# USB.net
KiCad netlist of a schematic drawn in Altium Designer
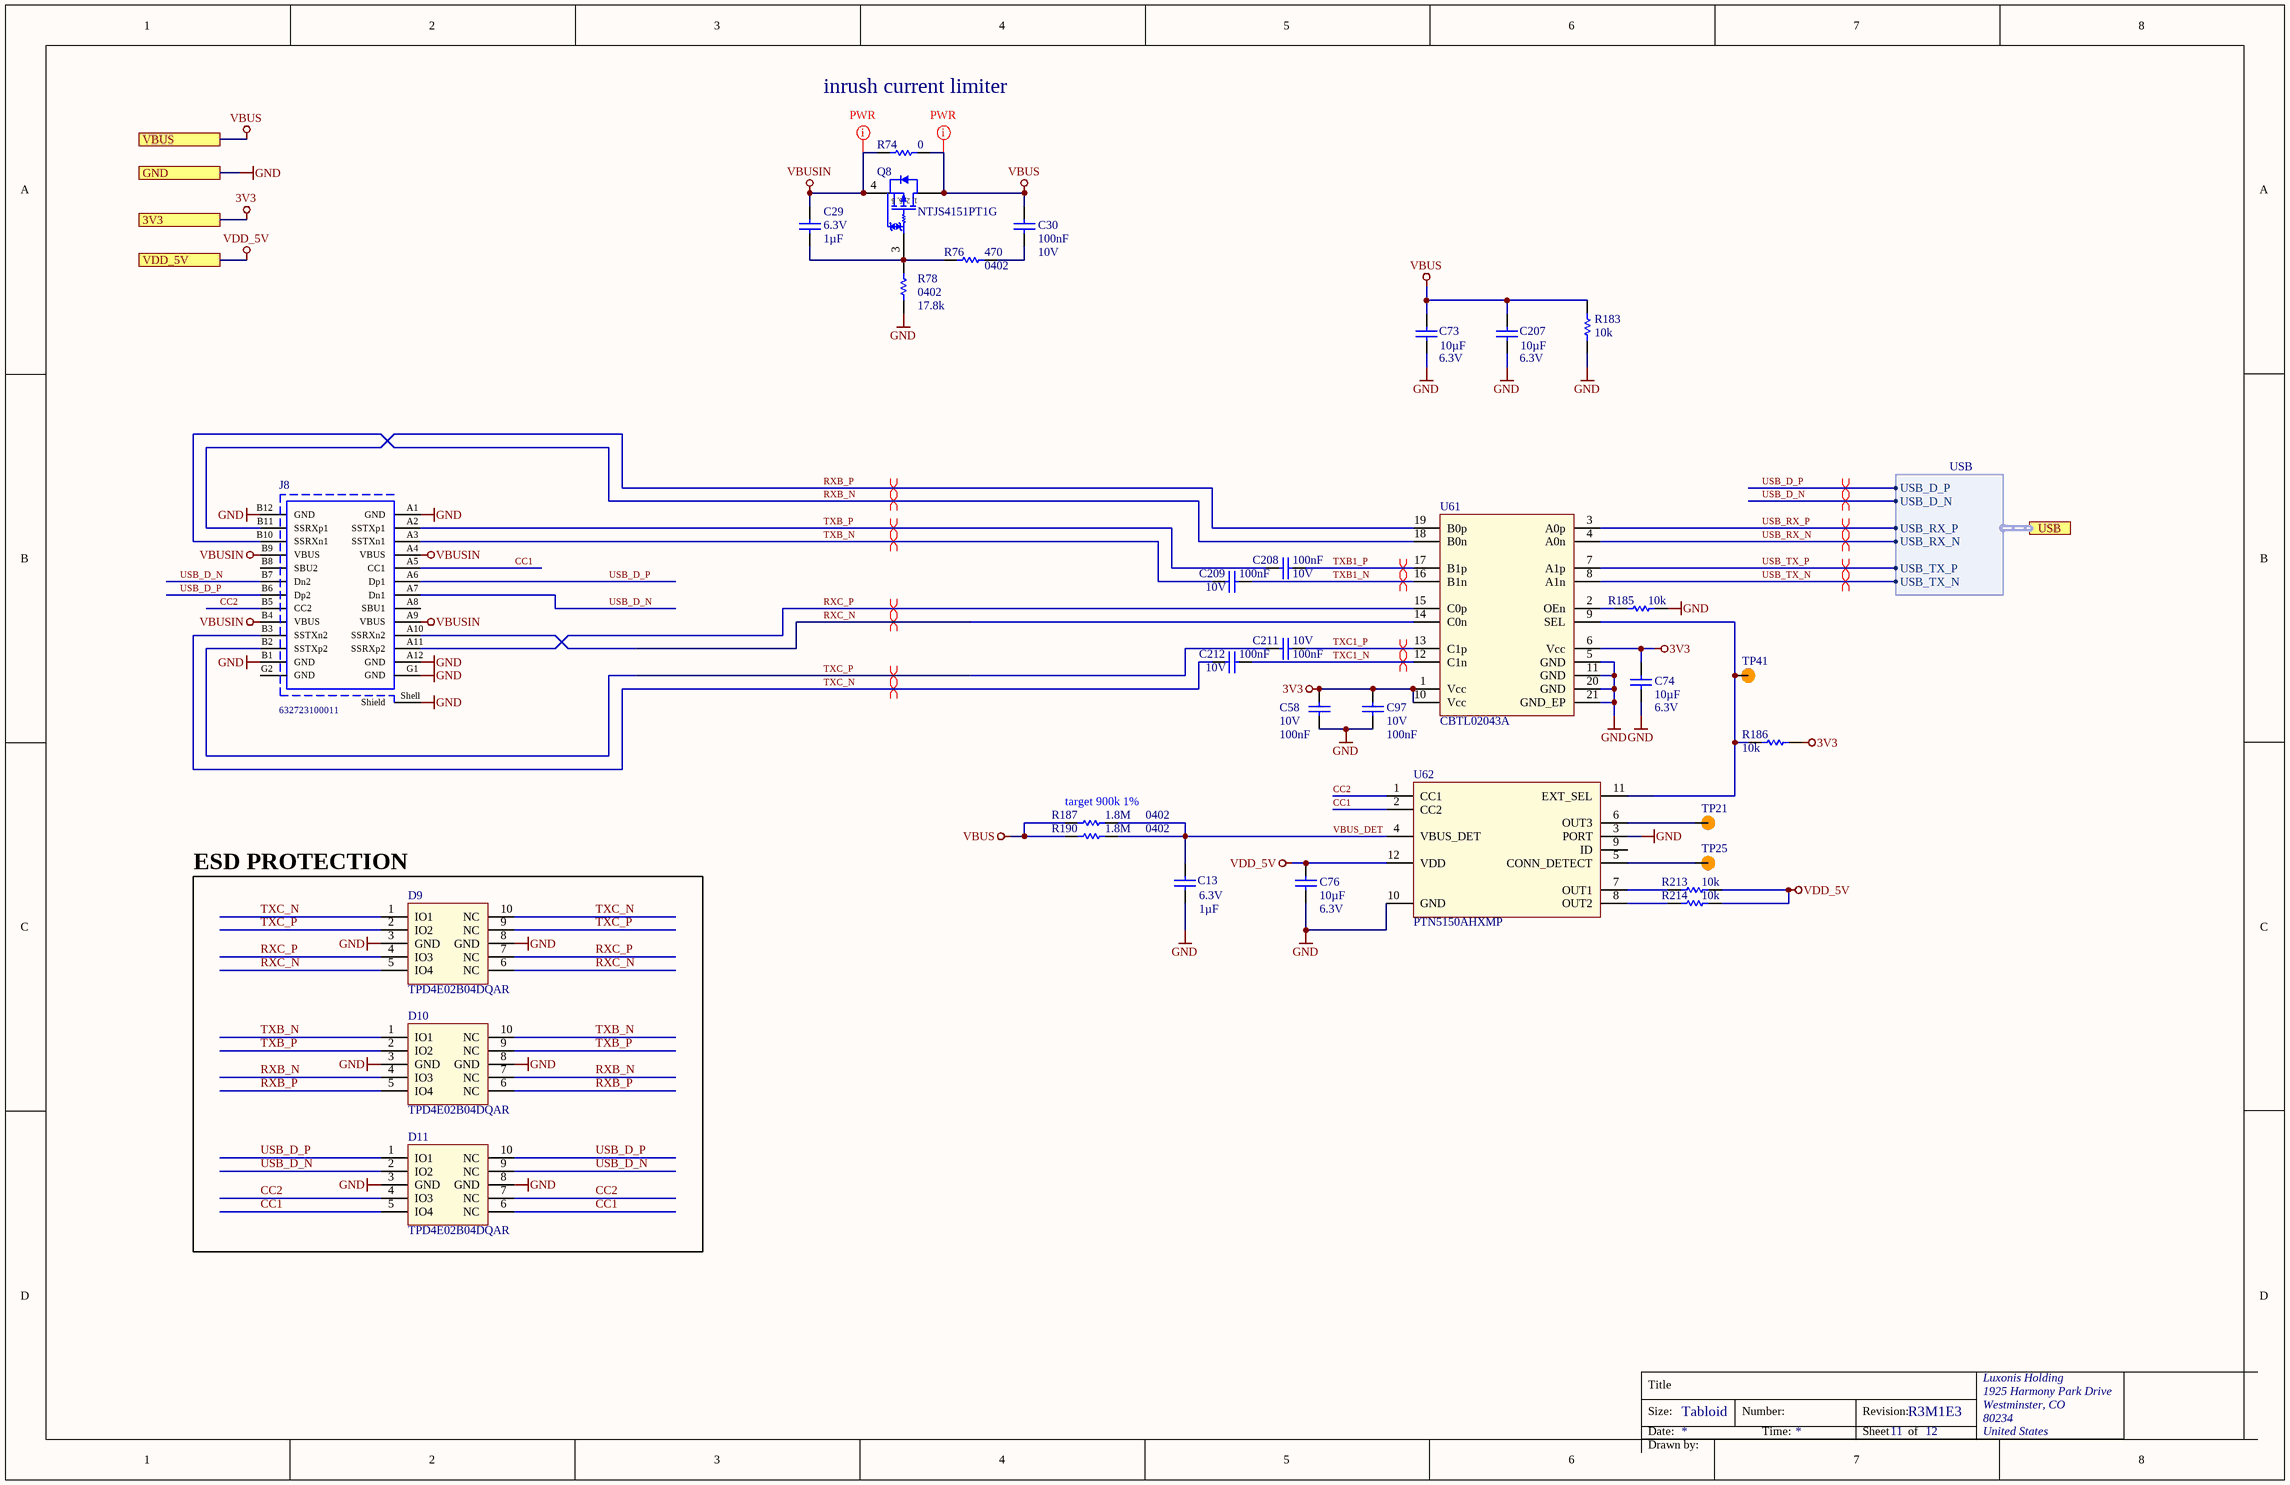
[diagram p0: USB.SchDoc]

(export (version "E")
  (design (tool "Eeschema 10.0.6"))
  (components
    (comp (ref "C13")
      (value "1µF")
      (footprint "CAPC0201(0603)33_L")
      (description "CAP CER 1UF 6.3V X5R 0201 20%")
      (fields
        (field (name "TOLERANCE") "20%")
        (field (name "VOLTAGE RATING") "6.3V")
        (field (name "Comment") "GRM033R60J105MEA2D")
      )
      (libsource (lib "Luxonis LLC") (part "LLL153C70G474ME17E"))
    )
    (comp (ref "C29")
      (value "1µF")
      (footprint "CAPC0201(0603)33_L")
      (description "CAP CER 1UF 6.3V X5R 0201 20%")
      (fields
        (field (name "TOLERANCE") "20%")
        (field (name "VOLTAGE RATING") "6.3V")
        (field (name "Comment") "GRM033R60J105MEA2D")
      )
      (libsource (lib "Luxonis LLC") (part "LLL153C70G474ME17E"))
    )
    (comp (ref "C30")
      (value "100nF")
      (footprint "CAPC0201(0603)33_L")
      (description "CAP CER 0.1UF 10V X5R 0201 10%")
      (fields
        (field (name "TOLERANCE") "10%")
        (field (name "VOLTAGE RATING") "10V")
        (field (name "Comment") "GRM033R61A104KE15D")
      )
      (libsource (lib "Luxonis LLC") (part "LLL153C70G474ME17E"))
    )
    (comp (ref "C58")
      (value "100nF")
      (footprint "CAPC0201(0603)33_L")
      (description "CAP CER 0.1UF 10V X5R 0201 10%")
      (fields
        (field (name "TOLERANCE") "10%")
        (field (name "VOLTAGE RATING") "10V")
        (field (name "Comment") "GRM033R61A104KE15D")
      )
      (libsource (lib "Luxonis LLC") (part "LLL153C70G474ME17E"))
    )
    (comp (ref "C73")
      (value "10µF")
      (footprint "CAPC0402(1005)70_N")
      (description "CAP CER 10UF 6.3V X5R 0402 20%")
      (fields
        (field (name "TOLERANCE") "20%")
        (field (name "VOLTAGE RATING") "6.3V")
        (field (name "Comment") "GRM155R60J106ME15D")
      )
      (libsource (lib "Luxonis LLC") (part "LLL153C70G474ME17E"))
    )
    (comp (ref "C74")
      (value "10µF")
      (footprint "CAPC0402(1005)70_N")
      (description "CAP CER 10UF 6.3V X5R 0402 20%")
      (fields
        (field (name "TOLERANCE") "20%")
        (field (name "VOLTAGE RATING") "6.3V")
        (field (name "Comment") "GRM155R60J106ME15D")
      )
      (libsource (lib "Luxonis LLC") (part "LLL153C70G474ME17E"))
    )
    (comp (ref "C76")
      (value "10µF")
      (footprint "CAPC0402(1005)70_N")
      (description "CAP CER 10UF 6.3V X5R 0402 20%")
      (fields
        (field (name "TOLERANCE") "20%")
        (field (name "VOLTAGE RATING") "6.3V")
        (field (name "Comment") "GRM155R60J106ME15D")
      )
      (libsource (lib "Luxonis LLC") (part "LLL153C70G474ME17E"))
    )
    (comp (ref "C97")
      (value "100nF")
      (footprint "CAPC0201(0603)33_L")
      (description "CAP CER 0.1UF 10V X5R 0201 10%")
      (fields
        (field (name "TOLERANCE") "10%")
        (field (name "VOLTAGE RATING") "10V")
        (field (name "Comment") "GRM033R61A104KE15D")
      )
      (libsource (lib "Luxonis LLC") (part "LLL153C70G474ME17E"))
    )
    (comp (ref "C207")
      (value "10µF")
      (footprint "CAPC0402(1005)70_N")
      (description "CAP CER 10UF 6.3V X5R 0402 20%")
      (fields
        (field (name "TOLERANCE") "20%")
        (field (name "VOLTAGE RATING") "6.3V")
        (field (name "Comment") "GRM155R60J106ME15D")
      )
      (libsource (lib "Luxonis LLC") (part "LLL153C70G474ME17E"))
    )
    (comp (ref "C208")
      (value "100nF")
      (footprint "CAPC0201(0603)33_L")
      (description "CAP CER 0.1UF 10V X5R 0201 10%")
      (fields
        (field (name "TOLERANCE") "10%")
        (field (name "VOLTAGE RATING") "10V")
        (field (name "Comment") "GRM033R61A104KE15D")
      )
      (libsource (lib "Luxonis LLC") (part "LLL153C70G474ME17E"))
    )
    (comp (ref "C209")
      (value "100nF")
      (footprint "CAPC0201(0603)33_L")
      (description "CAP CER 0.1UF 10V X5R 0201 10%")
      (fields
        (field (name "TOLERANCE") "10%")
        (field (name "VOLTAGE RATING") "10V")
        (field (name "Comment") "GRM033R61A104KE15D")
      )
      (libsource (lib "Luxonis LLC") (part "LLL153C70G474ME17E"))
    )
    (comp (ref "C211")
      (value "100nF")
      (footprint "CAPC0201(0603)33_L")
      (description "CAP CER 0.1UF 10V X5R 0201 10%")
      (fields
        (field (name "TOLERANCE") "10%")
        (field (name "VOLTAGE RATING") "10V")
        (field (name "Comment") "GRM033R61A104KE15D")
      )
      (libsource (lib "Luxonis LLC") (part "LLL153C70G474ME17E"))
    )
    (comp (ref "C212")
      (value "100nF")
      (footprint "CAPC0201(0603)33_L")
      (description "CAP CER 0.1UF 10V X5R 0201 10%")
      (fields
        (field (name "TOLERANCE") "10%")
        (field (name "VOLTAGE RATING") "10V")
        (field (name "Comment") "GRM033R61A104KE15D")
      )
      (libsource (lib "Luxonis LLC") (part "LLL153C70G474ME17E"))
    )
    (comp (ref "D9")
      (value "TPD4E02B04DQAR")
      (footprint "TPD4E02B04DQAR")
      (libsource (lib "Luxonis LLC") (part "TPD4E02B04DQAR"))
    )
    (comp (ref "D10")
      (value "TPD4E02B04DQAR")
      (footprint "TPD4E02B04DQAR")
      (libsource (lib "Luxonis LLC") (part "TPD4E02B04DQAR"))
    )
    (comp (ref "D11")
      (value "TPD4E02B04DQAR")
      (footprint "TPD4E02B04DQAR")
      (libsource (lib "Luxonis LLC") (part "TPD4E02B04DQAR"))
    )
    (comp (ref "J8")
      (value "632723100011")
      (footprint "632723100011")
      (libsource (lib "Luxonis LLC") (part "WE-632723X00011"))
    )
    (comp (ref "Q8")
      (value "NTJS4151PT1G")
      (footprint "ONSC-SC70-6-419B-02_W_V")
      (description "Trench Power MOSFET, -20 V, -4.2 A, Single P-Channel, 6-Pin SC70, Pb-Free, Tape and Reel")
      (libsource (lib "Luxonis LLC") (part "NTJS4151PT1G"))
    )
    (comp (ref "R74")
      (value "0")
      (footprint "RESC0603(1608)_L")
      (description "RES SMD 0 OHM 5% 1/10W 0603")
      (fields (field (name "TOLERANCE") "5%") (field (name "Comment") "CRCW06030000Z0EA"))
      (libsource (lib "Luxonis LLC") (part "RC0402FR-0722RL_1"))
    )
    (comp (ref "R76")
      (value "470")
      (footprint "RESC0402(1005)_L")
      (description "RES SMD 470 OHM 1% 1/16W 0402")
      (fields
        (field (name "CASE/PACKAGE") "0402")
        (field (name "TOLERANCE") "1%")
        (field (name "Comment") "CRCW0402470RFKED")
      )
      (libsource (lib "Luxonis LLC") (part "Default resistor symbol"))
    )
    (comp (ref "R78")
      (value "17.8k")
      (footprint "RESC0402(1005)_L")
      (description "RES SMD 17.8K OHM 1% 1/10W 0402")
      (fields
        (field (name "CASE/PACKAGE") "0402")
        (field (name "TOLERANCE") "1%")
        (field (name "Comment") "ERJ-2RKF1782X")
      )
      (libsource (lib "Luxonis LLC") (part "Default resistor symbol"))
    )
    (comp (ref "R183")
      (value "10k")
      (footprint "RESC0402(1005)_N")
      (description "RES SMD 10K OHM 1% 1/16W 0402")
      (fields (field (name "TOLERANCE") "1%") (field (name "Comment") "RC0402FR-1310KL"))
      (libsource (lib "Luxonis LLC") (part "RC0402FR-0722RL_1"))
    )
    (comp (ref "R185")
      (value "10k")
      (footprint "RESC0402(1005)_N")
      (description "RES SMD 10K OHM 1% 1/16W 0402")
      (fields (field (name "TOLERANCE") "1%") (field (name "Comment") "RC0402FR-1310KL"))
      (libsource (lib "Luxonis LLC") (part "RC0402FR-0722RL_1"))
    )
    (comp (ref "R186")
      (value "10k")
      (footprint "RESC0402(1005)_N")
      (description "RES SMD 10K OHM 1% 1/16W 0402")
      (fields (field (name "TOLERANCE") "1%") (field (name "Comment") "RC0402FR-1310KL"))
      (libsource (lib "Luxonis LLC") (part "RC0402FR-0722RL_1"))
    )
    (comp (ref "R187")
      (value "1.8M")
      (footprint "RESC0402(1005)_N")
      (description "RES SMD 1.8M OHM 1% 1/16W 0402")
      (fields
        (field (name "CASE/PACKAGE") "0402")
        (field (name "TOLERANCE") "1%")
        (field (name "Comment") "CRCW04021M80FKED")
      )
      (libsource (lib "Luxonis LLC") (part "Default resistor symbol"))
    )
    (comp (ref "R190")
      (value "1.8M")
      (footprint "RESC0402(1005)_N")
      (description "RES SMD 1.8M OHM 1% 1/16W 0402")
      (fields
        (field (name "CASE/PACKAGE") "0402")
        (field (name "TOLERANCE") "1%")
        (field (name "Comment") "CRCW04021M80FKED")
      )
      (libsource (lib "Luxonis LLC") (part "Default resistor symbol"))
    )
    (comp (ref "R213")
      (value "10k")
      (footprint "RESC0402(1005)_N")
      (description "RES SMD 10K OHM 1% 1/16W 0402")
      (fields (field (name "TOLERANCE") "1%") (field (name "Comment") "RC0402FR-1310KL"))
      (libsource (lib "Luxonis LLC") (part "RC0402FR-0722RL_1"))
    )
    (comp (ref "R214")
      (value "10k")
      (footprint "RESC0402(1005)_N")
      (description "RES SMD 10K OHM 1% 1/16W 0402")
      (fields (field (name "TOLERANCE") "1%") (field (name "Comment") "RC0402FR-1310KL"))
      (libsource (lib "Luxonis LLC") (part "RC0402FR-0722RL_1"))
    )
    (comp (ref "TP21")
      (value "TEST_POINT")
      (footprint "TP075_150_NS")
      (libsource (lib "Luxonis LLC") (part "TEST_POINT"))
    )
    (comp (ref "TP25")
      (value "TEST_POINT")
      (footprint "TP075_150_NS")
      (libsource (lib "Luxonis LLC") (part "TEST_POINT"))
    )
    (comp (ref "TP41")
      (value "TEST_POINT")
      (footprint "TP075_150_NS")
      (libsource (lib "Luxonis LLC") (part "TEST_POINT"))
    )
    (comp (ref "U61")
      (value "CBTL02043A")
      (footprint "CBTL02043A")
      (libsource (lib "Luxonis LLC") (part "CBTL02043A"))
    )
    (comp (ref "U62")
      (value "PTN5150AHXMP")
      (footprint "PTN5150H")
      (description "Power Supply Support Circuit, Fixed, 2 Channel, 0.2, PQCC12")
      (libsource (lib "Luxonis LLC") (part "PTN5150A"))
    )
  )
  (nets
    (net (code "2") (name "/CC1") (class "Default")
      (node (ref "D11") (pin "5") (pinfunction "IO4_5") (pintype "passive"))
      (node (ref "D11") (pin "6") (pinfunction "NC_6") (pintype "passive"))
      (node (ref "J8") (pin "A5") (pinfunction "CC1_A5") (pintype "passive"))
      (node (ref "U62") (pin "2") (pinfunction "CC2_2") (pintype "passive"))
    )
    (net (code "3") (name "/CC2") (class "Default")
      (node (ref "D11") (pin "4") (pinfunction "IO3_4") (pintype "passive"))
      (node (ref "D11") (pin "7") (pinfunction "NC_7") (pintype "passive"))
      (node (ref "J8") (pin "B5") (pinfunction "CC2_B5") (pintype "passive"))
      (node (ref "U62") (pin "1") (pinfunction "CC1_1") (pintype "passive"))
    )
    (net (code "4") (name "/RXB_N") (class "Default")
      (node (ref "D10") (pin "4") (pinfunction "IO3_4") (pintype "passive"))
      (node (ref "D10") (pin "7") (pinfunction "NC_7") (pintype "passive"))
      (node (ref "J8") (pin "B10") (pinfunction "SSRXn1_B10") (pintype "passive"))
      (node (ref "U61") (pin "18") (pinfunction "B0n_18") (pintype "passive"))
    )
    (net (code "5") (name "/RXB_P") (class "Default")
      (node (ref "D10") (pin "5") (pinfunction "IO4_5") (pintype "passive"))
      (node (ref "D10") (pin "6") (pinfunction "NC_6") (pintype "passive"))
      (node (ref "J8") (pin "B11") (pinfunction "SSRXp1_B11") (pintype "passive"))
      (node (ref "U61") (pin "19") (pinfunction "B0p_19") (pintype "passive"))
    )
    (net (code "6") (name "/RXC_N") (class "Default")
      (node (ref "D9") (pin "5") (pinfunction "IO4_5") (pintype "passive"))
      (node (ref "D9") (pin "6") (pinfunction "NC_6") (pintype "passive"))
      (node (ref "J8") (pin "A10") (pinfunction "SSRXn2_A10") (pintype "passive"))
      (node (ref "U61") (pin "14") (pinfunction "C0n_14") (pintype "passive"))
    )
    (net (code "7") (name "/RXC_P") (class "Default")
      (node (ref "D9") (pin "4") (pinfunction "IO3_4") (pintype "passive"))
      (node (ref "D9") (pin "7") (pinfunction "NC_7") (pintype "passive"))
      (node (ref "J8") (pin "A11") (pinfunction "SSRXp2_A11") (pintype "passive"))
      (node (ref "U61") (pin "15") (pinfunction "C0p_15") (pintype "passive"))
    )
    (net (code "8") (name "/TXB1_N") (class "Default")
      (node (ref "C209") (pin "2") (pinfunction "2_2") (pintype "passive"))
      (node (ref "U61") (pin "16") (pinfunction "B1n_16") (pintype "passive"))
    )
    (net (code "9") (name "/TXB1_P") (class "Default")
      (node (ref "C208") (pin "2") (pinfunction "2_2") (pintype "passive"))
      (node (ref "U61") (pin "17") (pinfunction "B1p_17") (pintype "passive"))
    )
    (net (code "10") (name "/TXB_N") (class "Default")
      (node (ref "C209") (pin "1") (pinfunction "1_1") (pintype "passive"))
      (node (ref "D10") (pin "1") (pinfunction "IO1_1") (pintype "passive"))
      (node (ref "D10") (pin "10") (pinfunction "NC_10") (pintype "passive"))
      (node (ref "J8") (pin "A3") (pinfunction "SSTXn1_A3") (pintype "passive"))
    )
    (net (code "11") (name "/TXB_P") (class "Default")
      (node (ref "C208") (pin "1") (pinfunction "1_1") (pintype "passive"))
      (node (ref "D10") (pin "2") (pinfunction "IO2_2") (pintype "passive"))
      (node (ref "D10") (pin "9") (pinfunction "NC_9") (pintype "passive"))
      (node (ref "J8") (pin "A2") (pinfunction "SSTXp1_A2") (pintype "passive"))
    )
    (net (code "12") (name "/TXC1_N") (class "Default")
      (node (ref "C212") (pin "2") (pinfunction "2_2") (pintype "passive"))
      (node (ref "U61") (pin "12") (pinfunction "C1n_12") (pintype "passive"))
    )
    (net (code "13") (name "/TXC1_P") (class "Default")
      (node (ref "C211") (pin "2") (pinfunction "2_2") (pintype "passive"))
      (node (ref "U61") (pin "13") (pinfunction "C1p_13") (pintype "passive"))
    )
    (net (code "14") (name "/TXC_N") (class "Default")
      (node (ref "C212") (pin "1") (pinfunction "1_1") (pintype "passive"))
      (node (ref "D9") (pin "1") (pinfunction "IO1_1") (pintype "passive"))
      (node (ref "D9") (pin "10") (pinfunction "NC_10") (pintype "passive"))
      (node (ref "J8") (pin "B3") (pinfunction "SSTXn2_B3") (pintype "passive"))
    )
    (net (code "15") (name "/TXC_P") (class "Default")
      (node (ref "C211") (pin "1") (pinfunction "1_1") (pintype "passive"))
      (node (ref "D9") (pin "2") (pinfunction "IO2_2") (pintype "passive"))
      (node (ref "D9") (pin "9") (pinfunction "NC_9") (pintype "passive"))
      (node (ref "J8") (pin "B2") (pinfunction "SSTXp2_B2") (pintype "passive"))
    )
    (net (code "16") (name "/USB_D_N") (class "Default")
      (node (ref "D11") (pin "2") (pinfunction "IO2_2") (pintype "passive"))
      (node (ref "D11") (pin "9") (pinfunction "NC_9") (pintype "passive"))
      (node (ref "J8") (pin "A7") (pinfunction "Dn1_A7") (pintype "passive"))
      (node (ref "J8") (pin "B7") (pinfunction "Dn2_B7") (pintype "passive"))
    )
    (net (code "17") (name "/USB_D_P") (class "Default")
      (node (ref "D11") (pin "1") (pinfunction "IO1_1") (pintype "passive"))
      (node (ref "D11") (pin "10") (pinfunction "NC_10") (pintype "passive"))
      (node (ref "J8") (pin "A6") (pinfunction "Dp1_A6") (pintype "passive"))
      (node (ref "J8") (pin "B6") (pinfunction "Dp2_B6") (pintype "passive"))
    )
    (net (code "18") (name "/USB_RX_N") (class "Default")
      (node (ref "U61") (pin "4") (pinfunction "A0n_4") (pintype "passive"))
    )
    (net (code "19") (name "/USB_RX_P") (class "Default")
      (node (ref "U61") (pin "3") (pinfunction "A0p_3") (pintype "passive"))
    )
    (net (code "20") (name "/USB_TX_N") (class "Default")
      (node (ref "U61") (pin "8") (pinfunction "A1n_8") (pintype "passive"))
    )
    (net (code "21") (name "/USB_TX_P") (class "Default")
      (node (ref "U61") (pin "7") (pinfunction "A1p_7") (pintype "passive"))
    )
    (net (code "22") (name "/VBUS_DET") (class "Default")
      (node (ref "C13") (pin "2") (pinfunction "2_2") (pintype "passive"))
      (node (ref "R187") (pin "2") (pinfunction "2_2") (pintype "passive"))
      (node (ref "R190") (pin "2") (pinfunction "2_2") (pintype "passive"))
      (node (ref "U62") (pin "4") (pinfunction "VBUS_DET_4") (pintype "passive"))
    )
    (net (code "24") (name "3V3") (class "Default")
      (node (ref "C58") (pin "2") (pinfunction "2_2") (pintype "passive"))
      (node (ref "C74") (pin "2") (pinfunction "2_2") (pintype "passive"))
      (node (ref "C97") (pin "2") (pinfunction "2_2") (pintype "passive"))
      (node (ref "R186") (pin "2") (pinfunction "2_2") (pintype "passive"))
      (node (ref "U61") (pin "1") (pinfunction "Vcc_1") (pintype "passive"))
      (node (ref "U61") (pin "10") (pinfunction "Vcc_10") (pintype "passive"))
      (node (ref "U61") (pin "6") (pinfunction "Vcc_6") (pintype "passive"))
    )
    (net (code "25") (name "GND") (class "Default")
      (node (ref "C13") (pin "1") (pinfunction "1_1") (pintype "passive"))
      (node (ref "C207") (pin "1") (pinfunction "1_1") (pintype "passive"))
      (node (ref "C58") (pin "1") (pinfunction "1_1") (pintype "passive"))
      (node (ref "C73") (pin "1") (pinfunction "1_1") (pintype "passive"))
      (node (ref "C74") (pin "1") (pinfunction "1_1") (pintype "passive"))
      (node (ref "C76") (pin "1") (pinfunction "1_1") (pintype "passive"))
      (node (ref "C97") (pin "1") (pinfunction "1_1") (pintype "passive"))
      (node (ref "D10") (pin "3") (pinfunction "GND_3") (pintype "passive"))
      (node (ref "D10") (pin "8") (pinfunction "GND_8") (pintype "passive"))
      (node (ref "D11") (pin "3") (pinfunction "GND_3") (pintype "passive"))
      (node (ref "D11") (pin "8") (pinfunction "GND_8") (pintype "passive"))
      (node (ref "D9") (pin "3") (pinfunction "GND_3") (pintype "passive"))
      (node (ref "D9") (pin "8") (pinfunction "GND_8") (pintype "passive"))
      (node (ref "J8") (pin "A1") (pinfunction "GND_A1") (pintype "passive"))
      (node (ref "J8") (pin "A12") (pinfunction "GND_A12") (pintype "passive"))
      (node (ref "J8") (pin "B1") (pinfunction "GND_B1") (pintype "passive"))
      (node (ref "J8") (pin "B12") (pinfunction "GND_B12") (pintype "passive"))
      (node (ref "J8") (pin "G1") (pinfunction "GND_G1") (pintype "passive"))
      (node (ref "J8") (pin "Shell") (pinfunction "Shield_Shell") (pintype "passive"))
      (node (ref "R183") (pin "1") (pinfunction "1_1") (pintype "passive"))
      (node (ref "R185") (pin "2") (pinfunction "2_2") (pintype "passive"))
      (node (ref "R78") (pin "1") (pinfunction "1_1") (pintype "passive"))
      (node (ref "U61") (pin "11") (pinfunction "GND_11") (pintype "passive"))
      (node (ref "U61") (pin "20") (pinfunction "GND_20") (pintype "passive"))
      (node (ref "U61") (pin "21") (pinfunction "GND_EP_21") (pintype "passive"))
      (node (ref "U61") (pin "5") (pinfunction "GND_5") (pintype "passive"))
      (node (ref "U62") (pin "10") (pinfunction "GND_10") (pintype "passive"))
      (node (ref "U62") (pin "3") (pinfunction "PORT_3") (pintype "passive"))
    )
    (net (code "26") (name "Net-(C30-Pad1)") (class "Default")
      (node (ref "C30") (pin "1") (pinfunction "1_1") (pintype "passive"))
      (node (ref "R76") (pin "2") (pinfunction "2_2") (pintype "passive"))
    )
    (net (code "27") (name "Net-(Q8-G)") (class "Default")
      (node (ref "C29") (pin "1") (pinfunction "1_1") (pintype "passive"))
      (node (ref "Q8") (pin "3") (pinfunction "G_3") (pintype "passive"))
      (node (ref "R76") (pin "1") (pinfunction "1_1") (pintype "passive"))
      (node (ref "R78") (pin "2") (pinfunction "2_2") (pintype "passive"))
    )
    (net (code "28") (name "Net-(U61-OEn)") (class "Default")
      (node (ref "R185") (pin "1") (pinfunction "1_1") (pintype "passive"))
      (node (ref "U61") (pin "2") (pinfunction "OEn_2") (pintype "passive"))
    )
    (net (code "29") (name "Net-(U61-SEL)") (class "Default")
      (node (ref "R186") (pin "1") (pinfunction "1_1") (pintype "passive"))
      (node (ref "TP41") (pin "1") (pintype "passive"))
      (node (ref "U61") (pin "9") (pinfunction "SEL_9") (pintype "passive"))
      (node (ref "U62") (pin "11") (pinfunction "EXT_SEL_11") (pintype "passive"))
    )
    (net (code "30") (name "Net-(U62-CONN_DETECT)") (class "Default")
      (node (ref "TP25") (pin "1") (pintype "passive"))
      (node (ref "U62") (pin "5") (pinfunction "CONN_DETECT_5") (pintype "passive"))
    )
    (net (code "31") (name "Net-(U62-OUT1)") (class "Default")
      (node (ref "R213") (pin "1") (pinfunction "1_1") (pintype "passive"))
      (node (ref "U62") (pin "7") (pinfunction "OUT1_7") (pintype "passive"))
    )
    (net (code "32") (name "Net-(U62-OUT2)") (class "Default")
      (node (ref "R214") (pin "1") (pinfunction "1_1") (pintype "passive"))
      (node (ref "U62") (pin "8") (pinfunction "OUT2_8") (pintype "passive"))
    )
    (net (code "33") (name "Net-(U62-OUT3)") (class "Default")
      (node (ref "TP21") (pin "1") (pintype "passive"))
      (node (ref "U62") (pin "6") (pinfunction "OUT3_6") (pintype "passive"))
    )
    (net (code "34") (name "VBUS") (class "Default")
      (node (ref "C207") (pin "2") (pinfunction "2_2") (pintype "passive"))
      (node (ref "C30") (pin "2") (pinfunction "2_2") (pintype "passive"))
      (node (ref "C73") (pin "2") (pinfunction "2_2") (pintype "passive"))
      (node (ref "Q8") (pin "1") (pinfunction "D_1") (pintype "passive"))
      (node (ref "Q8") (pin "2") (pinfunction "D_2") (pintype "passive"))
      (node (ref "Q8") (pin "5") (pinfunction "D_5") (pintype "passive"))
      (node (ref "Q8") (pin "6") (pinfunction "D_6") (pintype "passive"))
      (node (ref "R183") (pin "2") (pinfunction "2_2") (pintype "passive"))
      (node (ref "R187") (pin "1") (pinfunction "1_1") (pintype "passive"))
      (node (ref "R190") (pin "1") (pinfunction "1_1") (pintype "passive"))
      (node (ref "R74") (pin "2") (pinfunction "2_2") (pintype "passive"))
    )
    (net (code "35") (name "VBUSIN") (class "Default")
      (node (ref "C29") (pin "2") (pinfunction "2_2") (pintype "passive"))
      (node (ref "J8") (pin "A4") (pinfunction "VBUS_A4") (pintype "passive"))
      (node (ref "J8") (pin "A9") (pinfunction "VBUS_A9") (pintype "passive"))
      (node (ref "J8") (pin "B4") (pinfunction "VBUS_B4") (pintype "passive"))
      (node (ref "J8") (pin "B9") (pinfunction "VBUS_B9") (pintype "passive"))
      (node (ref "Q8") (pin "4") (pinfunction "S_4") (pintype "passive"))
      (node (ref "R74") (pin "1") (pinfunction "1_1") (pintype "passive"))
    )
    (net (code "36") (name "VDD_5V") (class "Default")
      (node (ref "C76") (pin "2") (pinfunction "2_2") (pintype "passive"))
      (node (ref "R213") (pin "2") (pinfunction "2_2") (pintype "passive"))
      (node (ref "R214") (pin "2") (pinfunction "2_2") (pintype "passive"))
      (node (ref "U62") (pin "12") (pinfunction "VDD_12") (pintype "passive"))
    )
    (net (code "37") (name "unconnected-(J8-GND-PadG2)") (class "Default")
      (node (ref "J8") (pin "G2") (pinfunction "GND_G2") (pintype "passive"))
    )
    (net (code "38") (name "unconnected-(J8-SBU1-PadA8)") (class "Default")
      (node (ref "J8") (pin "A8") (pinfunction "SBU1_A8") (pintype "passive"))
    )
    (net (code "39") (name "unconnected-(J8-SBU2-PadB8)") (class "Default")
      (node (ref "J8") (pin "B8") (pinfunction "SBU2_B8") (pintype "passive"))
    )
    (net (code "40") (name "unconnected-(U62-ID-Pad9)") (class "Default")
      (node (ref "U62") (pin "9") (pinfunction "ID_9") (pintype "passive"))
    )
  )
)
